# untitled.net
KiCad netlist of a schematic drawn in EAGLE
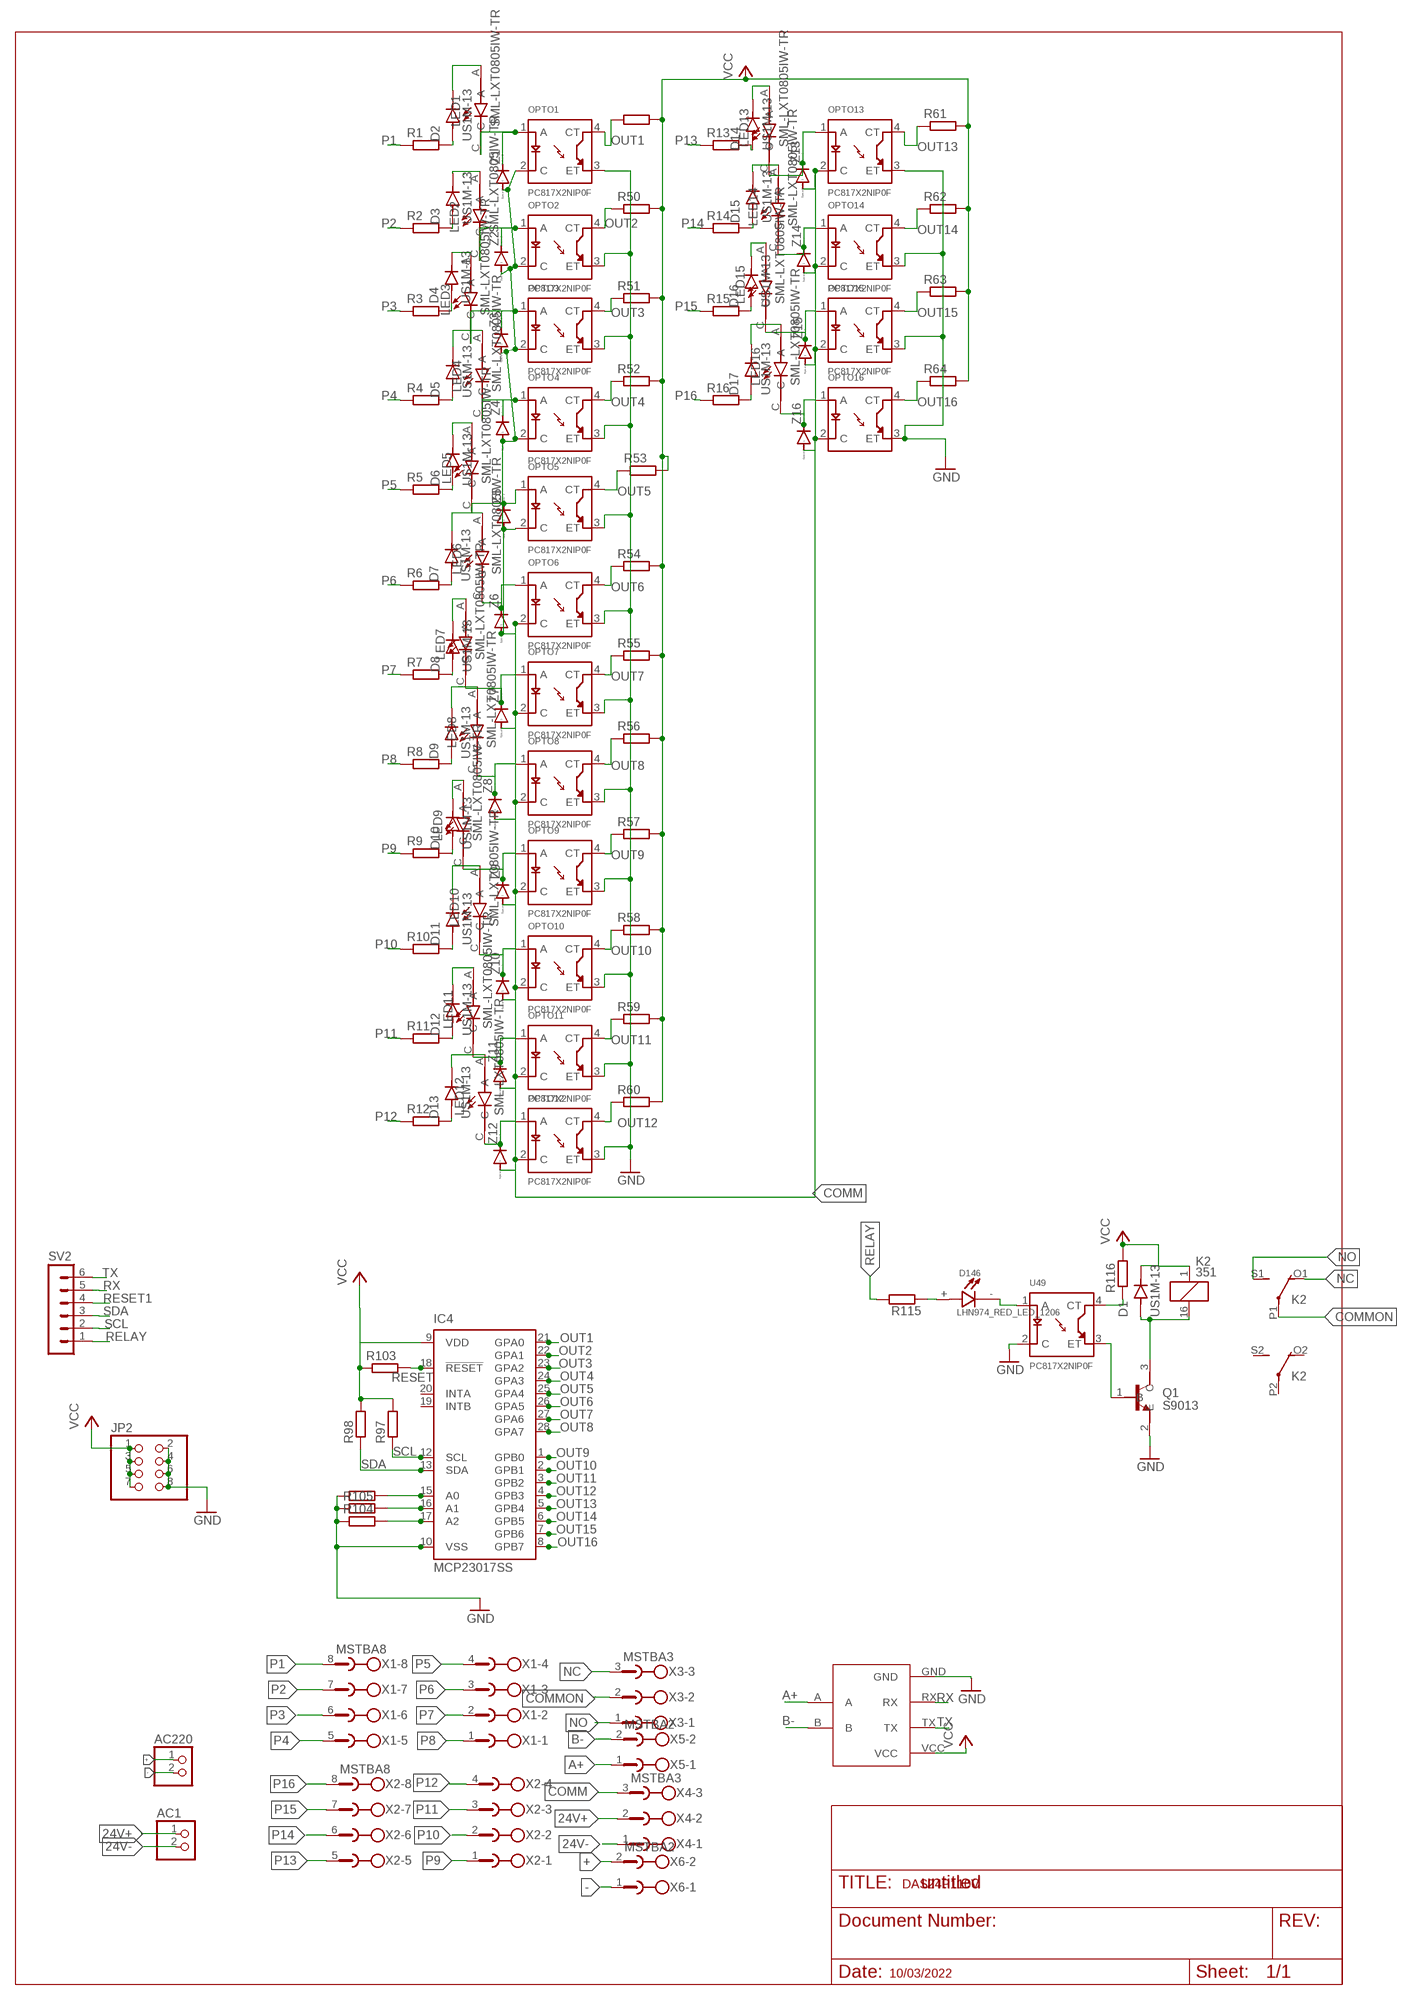
[diagram p0: schematic, sheet 1]

(export (version "E")
  (design (tool "Eeschema 10.0.6"))
  (components
    (comp (ref "AC1")
      (value "PINHD-1X2")
      (footprint "eagle-import:1X02")
      (libsource (lib "eagle-import") (part "PINHD-1X2"))
    )
    (comp (ref "AC220")
      (value "PINHD-1X2")
      (footprint "eagle-import:1X02")
      (libsource (lib "eagle-import") (part "PINHD-1X2"))
    )
    (comp (ref "D1")
      (value "US1M-13")
      (footprint "eagle-import:DIOM5226X240N")
      (fields (field (name "MF") "Diodes Incorporated"))
      (libsource (lib "eagle-import") (part "US1M-13"))
    )
    (comp (ref "D2")
      (value "US1M-13")
      (footprint "eagle-import:DIOM5226X240N")
      (fields (field (name "MF") "Diodes Incorporated"))
      (libsource (lib "eagle-import") (part "US1M-13"))
    )
    (comp (ref "D3")
      (value "US1M-13")
      (footprint "eagle-import:DIOM5226X240N")
      (fields (field (name "MF") "Diodes Incorporated"))
      (libsource (lib "eagle-import") (part "US1M-13"))
    )
    (comp (ref "D4")
      (value "US1M-13")
      (footprint "eagle-import:DIOM5226X240N")
      (fields (field (name "MF") "Diodes Incorporated"))
      (libsource (lib "eagle-import") (part "US1M-13"))
    )
    (comp (ref "D5")
      (value "US1M-13")
      (footprint "eagle-import:DIOM5226X240N")
      (fields (field (name "MF") "Diodes Incorporated"))
      (libsource (lib "eagle-import") (part "US1M-13"))
    )
    (comp (ref "D6")
      (value "US1M-13")
      (footprint "eagle-import:DIOM5226X240N")
      (fields (field (name "MF") "Diodes Incorporated"))
      (libsource (lib "eagle-import") (part "US1M-13"))
    )
    (comp (ref "D7")
      (value "US1M-13")
      (footprint "eagle-import:DIOM5226X240N")
      (fields (field (name "MF") "Diodes Incorporated"))
      (libsource (lib "eagle-import") (part "US1M-13"))
    )
    (comp (ref "D8")
      (value "US1M-13")
      (footprint "eagle-import:DIOM5226X240N")
      (fields (field (name "MF") "Diodes Incorporated"))
      (libsource (lib "eagle-import") (part "US1M-13"))
    )
    (comp (ref "D9")
      (value "US1M-13")
      (footprint "eagle-import:DIOM5226X240N")
      (fields (field (name "MF") "Diodes Incorporated"))
      (libsource (lib "eagle-import") (part "US1M-13"))
    )
    (comp (ref "D10")
      (value "US1M-13")
      (footprint "eagle-import:DIOM5226X240N")
      (fields (field (name "MF") "Diodes Incorporated"))
      (libsource (lib "eagle-import") (part "US1M-13"))
    )
    (comp (ref "D11")
      (value "US1M-13")
      (footprint "eagle-import:DIOM5226X240N")
      (fields (field (name "MF") "Diodes Incorporated"))
      (libsource (lib "eagle-import") (part "US1M-13"))
    )
    (comp (ref "D12")
      (value "US1M-13")
      (footprint "eagle-import:DIOM5226X240N")
      (fields (field (name "MF") "Diodes Incorporated"))
      (libsource (lib "eagle-import") (part "US1M-13"))
    )
    (comp (ref "D13")
      (value "US1M-13")
      (footprint "eagle-import:DIOM5226X240N")
      (fields (field (name "MF") "Diodes Incorporated"))
      (libsource (lib "eagle-import") (part "US1M-13"))
    )
    (comp (ref "D14")
      (value "US1M-13")
      (footprint "eagle-import:DIOM5226X240N")
      (fields (field (name "MF") "Diodes Incorporated"))
      (libsource (lib "eagle-import") (part "US1M-13"))
    )
    (comp (ref "D15")
      (value "US1M-13")
      (footprint "eagle-import:DIOM5226X240N")
      (fields (field (name "MF") "Diodes Incorporated"))
      (libsource (lib "eagle-import") (part "US1M-13"))
    )
    (comp (ref "D16")
      (value "US1M-13")
      (footprint "eagle-import:DIOM5226X240N")
      (fields (field (name "MF") "Diodes Incorporated"))
      (libsource (lib "eagle-import") (part "US1M-13"))
    )
    (comp (ref "D17")
      (value "US1M-13")
      (footprint "eagle-import:DIOM5226X240N")
      (fields (field (name "MF") "Diodes Incorporated"))
      (libsource (lib "eagle-import") (part "US1M-13"))
    )
    (comp (ref "D146")
      (value "LHN974_RED_LED_1206")
      (footprint "eagle-import:LEDC3216X120N")
      (fields (field (name "MF") "Osram") (field (name "MP") "LHN974 RED LED 1206"))
      (libsource (lib "eagle-import") (part "LHN974_RED_LED_1206"))
    )
    (comp (ref "IC4")
      (value "MCP23017SS")
      (footprint "eagle-import:SSOP28DB")
      (libsource (lib "eagle-import") (part "MCP23017SS"))
    )
    (comp (ref "JP2")
      (value "PINHD-2X4")
      (footprint "eagle-import:2X04")
      (libsource (lib "eagle-import") (part "PINHD-2X4"))
    )
    (comp (ref "K2")
      (value "351")
      (footprint "eagle-import:351")
      (libsource (lib "eagle-import") (part "351"))
    )
    (comp (ref "LED1")
      (value "SML-LXT0805IW-TR")
      (footprint "eagle-import:LEDC2012X120N")
      (fields (field (name "MF") "Lumex Opto/Components"))
      (libsource (lib "eagle-import") (part "SML-LXT0805IW-TR"))
    )
    (comp (ref "LED2")
      (value "SML-LXT0805IW-TR")
      (footprint "eagle-import:LEDC2012X120N")
      (fields (field (name "MF") "Lumex Opto/Components"))
      (libsource (lib "eagle-import") (part "SML-LXT0805IW-TR"))
    )
    (comp (ref "LED3")
      (value "SML-LXT0805IW-TR")
      (footprint "eagle-import:LEDC2012X120N")
      (fields (field (name "MF") "Lumex Opto/Components"))
      (libsource (lib "eagle-import") (part "SML-LXT0805IW-TR"))
    )
    (comp (ref "LED4")
      (value "SML-LXT0805IW-TR")
      (footprint "eagle-import:LEDC2012X120N")
      (fields (field (name "MF") "Lumex Opto/Components"))
      (libsource (lib "eagle-import") (part "SML-LXT0805IW-TR"))
    )
    (comp (ref "LED5")
      (value "SML-LXT0805IW-TR")
      (footprint "eagle-import:LEDC2012X120N")
      (fields (field (name "MF") "Lumex Opto/Components"))
      (libsource (lib "eagle-import") (part "SML-LXT0805IW-TR"))
    )
    (comp (ref "LED6")
      (value "SML-LXT0805IW-TR")
      (footprint "eagle-import:LEDC2012X120N")
      (fields (field (name "MF") "Lumex Opto/Components"))
      (libsource (lib "eagle-import") (part "SML-LXT0805IW-TR"))
    )
    (comp (ref "LED7")
      (value "SML-LXT0805IW-TR")
      (footprint "eagle-import:LEDC2012X120N")
      (fields (field (name "MF") "Lumex Opto/Components"))
      (libsource (lib "eagle-import") (part "SML-LXT0805IW-TR"))
    )
    (comp (ref "LED8")
      (value "SML-LXT0805IW-TR")
      (footprint "eagle-import:LEDC2012X120N")
      (fields (field (name "MF") "Lumex Opto/Components"))
      (libsource (lib "eagle-import") (part "SML-LXT0805IW-TR"))
    )
    (comp (ref "LED9")
      (value "SML-LXT0805IW-TR")
      (footprint "eagle-import:LEDC2012X120N")
      (fields (field (name "MF") "Lumex Opto/Components"))
      (libsource (lib "eagle-import") (part "SML-LXT0805IW-TR"))
    )
    (comp (ref "LED10")
      (value "SML-LXT0805IW-TR")
      (footprint "eagle-import:LEDC2012X120N")
      (fields (field (name "MF") "Lumex Opto/Components"))
      (libsource (lib "eagle-import") (part "SML-LXT0805IW-TR"))
    )
    (comp (ref "LED11")
      (value "SML-LXT0805IW-TR")
      (footprint "eagle-import:LEDC2012X120N")
      (fields (field (name "MF") "Lumex Opto/Components"))
      (libsource (lib "eagle-import") (part "SML-LXT0805IW-TR"))
    )
    (comp (ref "LED12")
      (value "SML-LXT0805IW-TR")
      (footprint "eagle-import:LEDC2012X120N")
      (fields (field (name "MF") "Lumex Opto/Components"))
      (libsource (lib "eagle-import") (part "SML-LXT0805IW-TR"))
    )
    (comp (ref "LED13")
      (value "SML-LXT0805IW-TR")
      (footprint "eagle-import:LEDC2012X120N")
      (fields (field (name "MF") "Lumex Opto/Components"))
      (libsource (lib "eagle-import") (part "SML-LXT0805IW-TR"))
    )
    (comp (ref "LED14")
      (value "SML-LXT0805IW-TR")
      (footprint "eagle-import:LEDC2012X120N")
      (fields (field (name "MF") "Lumex Opto/Components"))
      (libsource (lib "eagle-import") (part "SML-LXT0805IW-TR"))
    )
    (comp (ref "LED15")
      (value "SML-LXT0805IW-TR")
      (footprint "eagle-import:LEDC2012X120N")
      (fields (field (name "MF") "Lumex Opto/Components"))
      (libsource (lib "eagle-import") (part "SML-LXT0805IW-TR"))
    )
    (comp (ref "LED16")
      (value "SML-LXT0805IW-TR")
      (footprint "eagle-import:LEDC2012X120N")
      (fields (field (name "MF") "Lumex Opto/Components"))
      (libsource (lib "eagle-import") (part "SML-LXT0805IW-TR"))
    )
    (comp (ref "OPTO1")
      (value "PC817X2NIP0F")
      (footprint "eagle-import:SOT254P975X400-4N")
      (fields (field (name "MF") "Sharp Microelectronics"))
      (libsource (lib "eagle-import") (part "PC817X2NIP0F"))
    )
    (comp (ref "OPTO2")
      (value "PC817X2NIP0F")
      (footprint "eagle-import:SOT254P975X400-4N")
      (fields (field (name "MF") "Sharp Microelectronics"))
      (libsource (lib "eagle-import") (part "PC817X2NIP0F"))
    )
    (comp (ref "OPTO3")
      (value "PC817X2NIP0F")
      (footprint "eagle-import:SOT254P975X400-4N")
      (fields (field (name "MF") "Sharp Microelectronics"))
      (libsource (lib "eagle-import") (part "PC817X2NIP0F"))
    )
    (comp (ref "OPTO4")
      (value "PC817X2NIP0F")
      (footprint "eagle-import:SOT254P975X400-4N")
      (fields (field (name "MF") "Sharp Microelectronics"))
      (libsource (lib "eagle-import") (part "PC817X2NIP0F"))
    )
    (comp (ref "OPTO5")
      (value "PC817X2NIP0F")
      (footprint "eagle-import:SOT254P975X400-4N")
      (fields (field (name "MF") "Sharp Microelectronics"))
      (libsource (lib "eagle-import") (part "PC817X2NIP0F"))
    )
    (comp (ref "OPTO6")
      (value "PC817X2NIP0F")
      (footprint "eagle-import:SOT254P975X400-4N")
      (fields (field (name "MF") "Sharp Microelectronics"))
      (libsource (lib "eagle-import") (part "PC817X2NIP0F"))
    )
    (comp (ref "OPTO7")
      (value "PC817X2NIP0F")
      (footprint "eagle-import:SOT254P975X400-4N")
      (fields (field (name "MF") "Sharp Microelectronics"))
      (libsource (lib "eagle-import") (part "PC817X2NIP0F"))
    )
    (comp (ref "OPTO8")
      (value "PC817X2NIP0F")
      (footprint "eagle-import:SOT254P975X400-4N")
      (fields (field (name "MF") "Sharp Microelectronics"))
      (libsource (lib "eagle-import") (part "PC817X2NIP0F"))
    )
    (comp (ref "OPTO9")
      (value "PC817X2NIP0F")
      (footprint "eagle-import:SOT254P975X400-4N")
      (fields (field (name "MF") "Sharp Microelectronics"))
      (libsource (lib "eagle-import") (part "PC817X2NIP0F"))
    )
    (comp (ref "OPTO10")
      (value "PC817X2NIP0F")
      (footprint "eagle-import:SOT254P975X400-4N")
      (fields (field (name "MF") "Sharp Microelectronics"))
      (libsource (lib "eagle-import") (part "PC817X2NIP0F"))
    )
    (comp (ref "OPTO11")
      (value "PC817X2NIP0F")
      (footprint "eagle-import:SOT254P975X400-4N")
      (fields (field (name "MF") "Sharp Microelectronics"))
      (libsource (lib "eagle-import") (part "PC817X2NIP0F"))
    )
    (comp (ref "OPTO12")
      (value "PC817X2NIP0F")
      (footprint "eagle-import:SOT254P975X400-4N")
      (fields (field (name "MF") "Sharp Microelectronics"))
      (libsource (lib "eagle-import") (part "PC817X2NIP0F"))
    )
    (comp (ref "OPTO13")
      (value "PC817X2NIP0F")
      (footprint "eagle-import:SOT254P975X400-4N")
      (fields (field (name "MF") "Sharp Microelectronics"))
      (libsource (lib "eagle-import") (part "PC817X2NIP0F"))
    )
    (comp (ref "OPTO14")
      (value "PC817X2NIP0F")
      (footprint "eagle-import:SOT254P975X400-4N")
      (fields (field (name "MF") "Sharp Microelectronics"))
      (libsource (lib "eagle-import") (part "PC817X2NIP0F"))
    )
    (comp (ref "OPTO15")
      (value "PC817X2NIP0F")
      (footprint "eagle-import:SOT254P975X400-4N")
      (fields (field (name "MF") "Sharp Microelectronics"))
      (libsource (lib "eagle-import") (part "PC817X2NIP0F"))
    )
    (comp (ref "OPTO16")
      (value "PC817X2NIP0F")
      (footprint "eagle-import:SOT254P975X400-4N")
      (fields (field (name "MF") "Sharp Microelectronics"))
      (libsource (lib "eagle-import") (part "PC817X2NIP0F"))
    )
    (comp (ref "Q1")
      (value "S9013")
      (footprint "eagle-import:SOT95P240X120-3N")
      (fields (field (name "MF") "JCET"))
      (libsource (lib "eagle-import") (part "S9013"))
    )
    (comp (ref "R1")
      (value "R-EU_0414/15")
      (footprint "eagle-import:0414_15")
      (libsource (lib "eagle-import") (part "R-EU_0414/15"))
    )
    (comp (ref "R2")
      (value "R-EU_0414/15")
      (footprint "eagle-import:0414_15")
      (libsource (lib "eagle-import") (part "R-EU_0414/15"))
    )
    (comp (ref "R3")
      (value "R-EU_0414/15")
      (footprint "eagle-import:0414_15")
      (libsource (lib "eagle-import") (part "R-EU_0414/15"))
    )
    (comp (ref "R4")
      (value "R-EU_0414/15")
      (footprint "eagle-import:0414_15")
      (libsource (lib "eagle-import") (part "R-EU_0414/15"))
    )
    (comp (ref "R5")
      (value "R-EU_0414/15")
      (footprint "eagle-import:0414_15")
      (libsource (lib "eagle-import") (part "R-EU_0414/15"))
    )
    (comp (ref "R6")
      (value "R-EU_0414/15")
      (footprint "eagle-import:0414_15")
      (libsource (lib "eagle-import") (part "R-EU_0414/15"))
    )
    (comp (ref "R7")
      (value "R-EU_0414/15")
      (footprint "eagle-import:0414_15")
      (libsource (lib "eagle-import") (part "R-EU_0414/15"))
    )
    (comp (ref "R8")
      (value "R-EU_0414/15")
      (footprint "eagle-import:0414_15")
      (libsource (lib "eagle-import") (part "R-EU_0414/15"))
    )
    (comp (ref "R9")
      (value "R-EU_0414/15")
      (footprint "eagle-import:0414_15")
      (libsource (lib "eagle-import") (part "R-EU_0414/15"))
    )
    (comp (ref "R10")
      (value "R-EU_0414/15")
      (footprint "eagle-import:0414_15")
      (libsource (lib "eagle-import") (part "R-EU_0414/15"))
    )
    (comp (ref "R11")
      (value "R-EU_0414/15")
      (footprint "eagle-import:0414_15")
      (libsource (lib "eagle-import") (part "R-EU_0414/15"))
    )
    (comp (ref "R12")
      (value "R-EU_0414/15")
      (footprint "eagle-import:0414_15")
      (libsource (lib "eagle-import") (part "R-EU_0414/15"))
    )
    (comp (ref "R13")
      (value "R-EU_0414/15")
      (footprint "eagle-import:0414_15")
      (libsource (lib "eagle-import") (part "R-EU_0414/15"))
    )
    (comp (ref "R14")
      (value "R-EU_0414/15")
      (footprint "eagle-import:0414_15")
      (libsource (lib "eagle-import") (part "R-EU_0414/15"))
    )
    (comp (ref "R15")
      (value "R-EU_0414/15")
      (footprint "eagle-import:0414_15")
      (libsource (lib "eagle-import") (part "R-EU_0414/15"))
    )
    (comp (ref "R16")
      (value "R-EU_0414/15")
      (footprint "eagle-import:0414_15")
      (libsource (lib "eagle-import") (part "R-EU_0414/15"))
    )
    (comp (ref "R49")
      (value "R-EU_R0805")
      (footprint "eagle-import:R0805")
      (libsource (lib "eagle-import") (part "R-EU_R0805"))
    )
    (comp (ref "R50")
      (value "R-EU_R0805")
      (footprint "eagle-import:R0805")
      (libsource (lib "eagle-import") (part "R-EU_R0805"))
    )
    (comp (ref "R51")
      (value "R-EU_R0805")
      (footprint "eagle-import:R0805")
      (libsource (lib "eagle-import") (part "R-EU_R0805"))
    )
    (comp (ref "R52")
      (value "R-EU_R0805")
      (footprint "eagle-import:R0805")
      (libsource (lib "eagle-import") (part "R-EU_R0805"))
    )
    (comp (ref "R53")
      (value "R-EU_R0805")
      (footprint "eagle-import:R0805")
      (libsource (lib "eagle-import") (part "R-EU_R0805"))
    )
    (comp (ref "R54")
      (value "R-EU_R0805")
      (footprint "eagle-import:R0805")
      (libsource (lib "eagle-import") (part "R-EU_R0805"))
    )
    (comp (ref "R55")
      (value "R-EU_R0805")
      (footprint "eagle-import:R0805")
      (libsource (lib "eagle-import") (part "R-EU_R0805"))
    )
    (comp (ref "R56")
      (value "R-EU_R0805")
      (footprint "eagle-import:R0805")
      (libsource (lib "eagle-import") (part "R-EU_R0805"))
    )
    (comp (ref "R57")
      (value "R-EU_R0805")
      (footprint "eagle-import:R0805")
      (libsource (lib "eagle-import") (part "R-EU_R0805"))
    )
    (comp (ref "R58")
      (value "R-EU_R0805")
      (footprint "eagle-import:R0805")
      (libsource (lib "eagle-import") (part "R-EU_R0805"))
    )
    (comp (ref "R59")
      (value "R-EU_R0805")
      (footprint "eagle-import:R0805")
      (libsource (lib "eagle-import") (part "R-EU_R0805"))
    )
    (comp (ref "R60")
      (value "R-EU_R0805")
      (footprint "eagle-import:R0805")
      (libsource (lib "eagle-import") (part "R-EU_R0805"))
    )
    (comp (ref "R61")
      (value "R-EU_R0805")
      (footprint "eagle-import:R0805")
      (libsource (lib "eagle-import") (part "R-EU_R0805"))
    )
    (comp (ref "R62")
      (value "R-EU_R0805")
      (footprint "eagle-import:R0805")
      (libsource (lib "eagle-import") (part "R-EU_R0805"))
    )
    (comp (ref "R63")
      (value "R-EU_R0805")
      (footprint "eagle-import:R0805")
      (libsource (lib "eagle-import") (part "R-EU_R0805"))
    )
    (comp (ref "R64")
      (value "R-EU_R0805")
      (footprint "eagle-import:R0805")
      (libsource (lib "eagle-import") (part "R-EU_R0805"))
    )
    (comp (ref "R97")
      (value "R-EU_R0805")
      (footprint "eagle-import:R0805")
      (libsource (lib "eagle-import") (part "R-EU_R0805"))
    )
    (comp (ref "R98")
      (value "R-EU_R0805")
      (footprint "eagle-import:R0805")
      (libsource (lib "eagle-import") (part "R-EU_R0805"))
    )
    (comp (ref "R103")
      (value "R-EU_R0805")
      (footprint "eagle-import:R0805")
      (libsource (lib "eagle-import") (part "R-EU_R0805"))
    )
    (comp (ref "R104")
      (value "R-EU_R0805")
      (footprint "eagle-import:R0805")
      (libsource (lib "eagle-import") (part "R-EU_R0805"))
    )
    (comp (ref "R105")
      (value "R-EU_R0805")
      (footprint "eagle-import:R0805")
      (libsource (lib "eagle-import") (part "R-EU_R0805"))
    )
    (comp (ref "R106")
      (value "R-EU_R0805")
      (footprint "eagle-import:R0805")
      (libsource (lib "eagle-import") (part "R-EU_R0805"))
    )
    (comp (ref "R115")
      (value "R-EU_R0805")
      (footprint "eagle-import:R0805")
      (libsource (lib "eagle-import") (part "R-EU_R0805"))
    )
    (comp (ref "R116")
      (value "R-EU_R0805")
      (footprint "eagle-import:R0805")
      (libsource (lib "eagle-import") (part "R-EU_R0805"))
    )
    (comp (ref "SV2")
      (value "MA06-1")
      (footprint "eagle-import:MA06-1")
      (libsource (lib "eagle-import") (part "MA06-1"))
    )
    (comp (ref "TTL-RS1")
      (value "TTL-RS485")
      (footprint "eagle-import:TTL-RS485")
      (libsource (lib "eagle-import") (part "TTL-RS485"))
    )
    (comp (ref "U49")
      (value "PC817X2NIP0F")
      (footprint "eagle-import:SOT254P975X400-4N")
      (fields (field (name "MF") "Sharp Microelectronics"))
      (libsource (lib "eagle-import") (part "PC817X2NIP0F"))
    )
    (comp (ref "X1")
      (value "MSTBA8")
      (footprint "eagle-import:MSTBA8")
      (fields (field (name "MF") "FARNELL") (field (name "MPN") "1757307"))
      (libsource (lib "eagle-import") (part "MSTBA8"))
    )
    (comp (ref "X2")
      (value "MSTBA8")
      (footprint "eagle-import:MSTBA8")
      (fields (field (name "MF") "FARNELL") (field (name "MPN") "1757307"))
      (libsource (lib "eagle-import") (part "MSTBA8"))
    )
    (comp (ref "X3")
      (value "MSTBA3")
      (footprint "eagle-import:MSTBA3")
      (fields (field (name "MF") "FARNELL") (field (name "MPN") "1757255"))
      (libsource (lib "eagle-import") (part "MSTBA3"))
    )
    (comp (ref "X4")
      (value "MSTBA3")
      (footprint "eagle-import:MSTBA3")
      (fields (field (name "MF") "FARNELL") (field (name "MPN") "1757255"))
      (libsource (lib "eagle-import") (part "MSTBA3"))
    )
    (comp (ref "X5")
      (value "MSTBA2")
      (footprint "eagle-import:MSTBA2")
      (fields (field (name "MF") "FARNELL") (field (name "MPN") "1757242"))
      (libsource (lib "eagle-import") (part "MSTBA2"))
    )
    (comp (ref "X6")
      (value "MSTBA2")
      (footprint "eagle-import:MSTBA2")
      (fields (field (name "MF") "FARNELL") (field (name "MPN") "1757242"))
      (libsource (lib "eagle-import") (part "MSTBA2"))
    )
    (comp (ref "Z1")
      (value "DIODE-SOD123")
      (footprint "eagle-import:SOD123")
      (libsource (lib "eagle-import") (part "DIODE-SOD123"))
    )
    (comp (ref "Z2")
      (value "DIODE-SOD123")
      (footprint "eagle-import:SOD123")
      (libsource (lib "eagle-import") (part "DIODE-SOD123"))
    )
    (comp (ref "Z3")
      (value "DIODE-SOD123")
      (footprint "eagle-import:SOD123")
      (libsource (lib "eagle-import") (part "DIODE-SOD123"))
    )
    (comp (ref "Z4")
      (value "DIODE-SOD123")
      (footprint "eagle-import:SOD123")
      (libsource (lib "eagle-import") (part "DIODE-SOD123"))
    )
    (comp (ref "Z5")
      (value "DIODE-SOD123")
      (footprint "eagle-import:SOD123")
      (libsource (lib "eagle-import") (part "DIODE-SOD123"))
    )
    (comp (ref "Z6")
      (value "DIODE-SOD123")
      (footprint "eagle-import:SOD123")
      (libsource (lib "eagle-import") (part "DIODE-SOD123"))
    )
    (comp (ref "Z7")
      (value "DIODE-SOD123")
      (footprint "eagle-import:SOD123")
      (libsource (lib "eagle-import") (part "DIODE-SOD123"))
    )
    (comp (ref "Z8")
      (value "DIODE-SOD123")
      (footprint "eagle-import:SOD123")
      (libsource (lib "eagle-import") (part "DIODE-SOD123"))
    )
    (comp (ref "Z9")
      (value "DIODE-SOD123")
      (footprint "eagle-import:SOD123")
      (libsource (lib "eagle-import") (part "DIODE-SOD123"))
    )
    (comp (ref "Z10")
      (value "DIODE-SOD123")
      (footprint "eagle-import:SOD123")
      (libsource (lib "eagle-import") (part "DIODE-SOD123"))
    )
    (comp (ref "Z11")
      (value "DIODE-SOD123")
      (footprint "eagle-import:SOD123")
      (libsource (lib "eagle-import") (part "DIODE-SOD123"))
    )
    (comp (ref "Z12")
      (value "DIODE-SOD123")
      (footprint "eagle-import:SOD123")
      (libsource (lib "eagle-import") (part "DIODE-SOD123"))
    )
    (comp (ref "Z13")
      (value "DIODE-SOD123")
      (footprint "eagle-import:SOD123")
      (libsource (lib "eagle-import") (part "DIODE-SOD123"))
    )
    (comp (ref "Z14")
      (value "DIODE-SOD123")
      (footprint "eagle-import:SOD123")
      (libsource (lib "eagle-import") (part "DIODE-SOD123"))
    )
    (comp (ref "Z15")
      (value "DIODE-SOD123")
      (footprint "eagle-import:SOD123")
      (libsource (lib "eagle-import") (part "DIODE-SOD123"))
    )
    (comp (ref "Z16")
      (value "DIODE-SOD123")
      (footprint "eagle-import:SOD123")
      (libsource (lib "eagle-import") (part "DIODE-SOD123"))
    )
  )
  (nets
    (net (code "1") (name "+") (class "Default")
      (node (ref "AC220") (pin "1") (pinfunction "1_1") (pintype "passive"))
      (node (ref "X6") (pin "2") (pinfunction "1_2") (pintype "passive"))
    )
    (net (code "2") (name "-") (class "Default")
      (node (ref "AC220") (pin "2") (pinfunction "2_2") (pintype "passive"))
      (node (ref "X6") (pin "1") (pinfunction "1_1") (pintype "passive"))
    )
    (net (code "3") (name "/OUT1") (class "Default")
      (node (ref "IC4") (pin "21") (pinfunction "GPA0_21") (pintype "bidirectional"))
      (node (ref "OPTO1") (pin "4") (pinfunction "CT_4") (pintype "passive"))
      (node (ref "R49") (pin "1") (pinfunction "1_1") (pintype "passive"))
    )
    (net (code "4") (name "/OUT2") (class "Default")
      (node (ref "IC4") (pin "22") (pinfunction "GPA1_22") (pintype "bidirectional"))
      (node (ref "OPTO2") (pin "4") (pinfunction "CT_4") (pintype "passive"))
      (node (ref "R50") (pin "1") (pinfunction "1_1") (pintype "passive"))
    )
    (net (code "5") (name "/OUT3") (class "Default")
      (node (ref "IC4") (pin "23") (pinfunction "GPA2_23") (pintype "bidirectional"))
      (node (ref "OPTO3") (pin "4") (pinfunction "CT_4") (pintype "passive"))
      (node (ref "R51") (pin "1") (pinfunction "1_1") (pintype "passive"))
    )
    (net (code "6") (name "/OUT4") (class "Default")
      (node (ref "IC4") (pin "24") (pinfunction "GPA3_24") (pintype "bidirectional"))
      (node (ref "OPTO4") (pin "4") (pinfunction "CT_4") (pintype "passive"))
      (node (ref "R52") (pin "1") (pinfunction "1_1") (pintype "passive"))
    )
    (net (code "7") (name "/OUT5") (class "Default")
      (node (ref "IC4") (pin "25") (pinfunction "GPA4_25") (pintype "bidirectional"))
      (node (ref "OPTO5") (pin "4") (pinfunction "CT_4") (pintype "passive"))
      (node (ref "R53") (pin "1") (pinfunction "1_1") (pintype "passive"))
    )
    (net (code "8") (name "/OUT6") (class "Default")
      (node (ref "IC4") (pin "26") (pinfunction "GPA5_26") (pintype "bidirectional"))
      (node (ref "OPTO6") (pin "4") (pinfunction "CT_4") (pintype "passive"))
      (node (ref "R54") (pin "1") (pinfunction "1_1") (pintype "passive"))
    )
    (net (code "9") (name "/OUT7") (class "Default")
      (node (ref "IC4") (pin "27") (pinfunction "GPA6_27") (pintype "bidirectional"))
      (node (ref "OPTO7") (pin "4") (pinfunction "CT_4") (pintype "passive"))
      (node (ref "R55") (pin "1") (pinfunction "1_1") (pintype "passive"))
    )
    (net (code "10") (name "/OUT8") (class "Default")
      (node (ref "IC4") (pin "28") (pinfunction "GPA7_28") (pintype "bidirectional"))
      (node (ref "OPTO8") (pin "4") (pinfunction "CT_4") (pintype "passive"))
      (node (ref "R56") (pin "1") (pinfunction "1_1") (pintype "passive"))
    )
    (net (code "11") (name "/OUT9") (class "Default")
      (node (ref "IC4") (pin "1") (pinfunction "GPB0_1") (pintype "bidirectional"))
      (node (ref "OPTO9") (pin "4") (pinfunction "CT_4") (pintype "passive"))
      (node (ref "R57") (pin "1") (pinfunction "1_1") (pintype "passive"))
    )
    (net (code "12") (name "/OUT10") (class "Default")
      (node (ref "IC4") (pin "2") (pinfunction "GPB1_2") (pintype "bidirectional"))
      (node (ref "OPTO10") (pin "4") (pinfunction "CT_4") (pintype "passive"))
      (node (ref "R58") (pin "1") (pinfunction "1_1") (pintype "passive"))
    )
    (net (code "13") (name "/OUT11") (class "Default")
      (node (ref "IC4") (pin "3") (pinfunction "GPB2_3") (pintype "bidirectional"))
      (node (ref "OPTO11") (pin "4") (pinfunction "CT_4") (pintype "passive"))
      (node (ref "R59") (pin "1") (pinfunction "1_1") (pintype "passive"))
    )
    (net (code "14") (name "/OUT12") (class "Default")
      (node (ref "IC4") (pin "4") (pinfunction "GPB3_4") (pintype "bidirectional"))
      (node (ref "OPTO12") (pin "4") (pinfunction "CT_4") (pintype "passive"))
      (node (ref "R60") (pin "1") (pinfunction "1_1") (pintype "passive"))
    )
    (net (code "15") (name "/OUT13") (class "Default")
      (node (ref "IC4") (pin "5") (pinfunction "GPB4_5") (pintype "bidirectional"))
      (node (ref "OPTO13") (pin "4") (pinfunction "CT_4") (pintype "passive"))
      (node (ref "R61") (pin "1") (pinfunction "1_1") (pintype "passive"))
    )
    (net (code "16") (name "/OUT14") (class "Default")
      (node (ref "IC4") (pin "6") (pinfunction "GPB5_6") (pintype "bidirectional"))
      (node (ref "OPTO14") (pin "4") (pinfunction "CT_4") (pintype "passive"))
      (node (ref "R62") (pin "1") (pinfunction "1_1") (pintype "passive"))
    )
    (net (code "17") (name "/OUT15") (class "Default")
      (node (ref "IC4") (pin "7") (pinfunction "GPB6_7") (pintype "bidirectional"))
      (node (ref "OPTO15") (pin "4") (pinfunction "CT_4") (pintype "passive"))
      (node (ref "R63") (pin "1") (pinfunction "1_1") (pintype "passive"))
    )
    (net (code "18") (name "/OUT16") (class "Default")
      (node (ref "IC4") (pin "8") (pinfunction "GPB7_8") (pintype "bidirectional"))
      (node (ref "OPTO16") (pin "4") (pinfunction "CT_4") (pintype "passive"))
      (node (ref "R64") (pin "1") (pinfunction "1_1") (pintype "passive"))
    )
    (net (code "19") (name "/RESET") (class "Default")
      (node (ref "IC4") (pin "18") (pinfunction "~{RESET}_18") (pintype "input"))
      (node (ref "R103") (pin "2") (pinfunction "2_2") (pintype "passive"))
    )
    (net (code "20") (name "/RESET1") (class "Default")
      (node (ref "SV2") (pin "4") (pinfunction "4_4") (pintype "passive"))
    )
    (net (code "21") (name "/RX") (class "Default")
      (node (ref "SV2") (pin "5") (pinfunction "5_5") (pintype "passive"))
      (node (ref "TTL-RS1") (pin "RX") (pinfunction "RX_RX") (pintype "bidirectional"))
    )
    (net (code "22") (name "/SCL") (class "Default")
      (node (ref "IC4") (pin "12") (pinfunction "SCL_12") (pintype "input"))
      (node (ref "R97") (pin "1") (pinfunction "1_1") (pintype "passive"))
      (node (ref "SV2") (pin "2") (pinfunction "2_2") (pintype "passive"))
    )
    (net (code "23") (name "/SDA") (class "Default")
      (node (ref "IC4") (pin "13") (pinfunction "SDA_13") (pintype "bidirectional"))
      (node (ref "R98") (pin "1") (pinfunction "1_1") (pintype "passive"))
      (node (ref "SV2") (pin "3") (pinfunction "3_3") (pintype "passive"))
    )
    (net (code "24") (name "/TX") (class "Default")
      (node (ref "SV2") (pin "6") (pinfunction "6_6") (pintype "passive"))
      (node (ref "TTL-RS1") (pin "TX") (pinfunction "TX_TX") (pintype "bidirectional"))
    )
    (net (code "25") (name "24V+") (class "Default")
      (node (ref "AC1") (pin "1") (pinfunction "1_1") (pintype "passive"))
      (node (ref "X4") (pin "2") (pinfunction "1_2") (pintype "passive"))
    )
    (net (code "26") (name "24V-") (class "Default")
      (node (ref "AC1") (pin "2") (pinfunction "2_2") (pintype "passive"))
      (node (ref "X4") (pin "1") (pinfunction "1_1") (pintype "passive"))
    )
    (net (code "27") (name "A+") (class "Default")
      (node (ref "TTL-RS1") (pin "A") (pinfunction "A_A") (pintype "bidirectional"))
      (node (ref "X5") (pin "1") (pinfunction "1_1") (pintype "passive"))
    )
    (net (code "28") (name "B-") (class "Default")
      (node (ref "TTL-RS1") (pin "B") (pinfunction "B_B") (pintype "bidirectional"))
      (node (ref "X5") (pin "2") (pinfunction "1_2") (pintype "passive"))
    )
    (net (code "29") (name "COMM") (class "Default")
      (node (ref "OPTO1") (pin "2") (pinfunction "C_2") (pintype "passive"))
      (node (ref "OPTO10") (pin "2") (pinfunction "C_2") (pintype "passive"))
      (node (ref "OPTO11") (pin "2") (pinfunction "C_2") (pintype "passive"))
      (node (ref "OPTO12") (pin "2") (pinfunction "C_2") (pintype "passive"))
      (node (ref "OPTO13") (pin "2") (pinfunction "C_2") (pintype "passive"))
      (node (ref "OPTO14") (pin "2") (pinfunction "C_2") (pintype "passive"))
      (node (ref "OPTO15") (pin "2") (pinfunction "C_2") (pintype "passive"))
      (node (ref "OPTO16") (pin "2") (pinfunction "C_2") (pintype "passive"))
      (node (ref "OPTO2") (pin "2") (pinfunction "C_2") (pintype "passive"))
      (node (ref "OPTO3") (pin "2") (pinfunction "C_2") (pintype "passive"))
      (node (ref "OPTO4") (pin "2") (pinfunction "C_2") (pintype "passive"))
      (node (ref "OPTO5") (pin "2") (pinfunction "C_2") (pintype "passive"))
      (node (ref "OPTO6") (pin "2") (pinfunction "C_2") (pintype "passive"))
      (node (ref "OPTO7") (pin "2") (pinfunction "C_2") (pintype "passive"))
      (node (ref "OPTO8") (pin "2") (pinfunction "C_2") (pintype "passive"))
      (node (ref "OPTO9") (pin "2") (pinfunction "C_2") (pintype "passive"))
      (node (ref "X4") (pin "3") (pinfunction "1_3") (pintype "passive"))
      (node (ref "Z1") (pin "A") (pinfunction "A_A") (pintype "passive"))
      (node (ref "Z10") (pin "A") (pinfunction "A_A") (pintype "passive"))
      (node (ref "Z11") (pin "A") (pinfunction "A_A") (pintype "passive"))
      (node (ref "Z12") (pin "A") (pinfunction "A_A") (pintype "passive"))
      (node (ref "Z13") (pin "A") (pinfunction "A_A") (pintype "passive"))
      (node (ref "Z14") (pin "A") (pinfunction "A_A") (pintype "passive"))
      (node (ref "Z15") (pin "A") (pinfunction "A_A") (pintype "passive"))
      (node (ref "Z16") (pin "A") (pinfunction "A_A") (pintype "passive"))
      (node (ref "Z2") (pin "A") (pinfunction "A_A") (pintype "passive"))
      (node (ref "Z3") (pin "A") (pinfunction "A_A") (pintype "passive"))
      (node (ref "Z4") (pin "A") (pinfunction "A_A") (pintype "passive"))
      (node (ref "Z5") (pin "A") (pinfunction "A_A") (pintype "passive"))
      (node (ref "Z6") (pin "A") (pinfunction "A_A") (pintype "passive"))
      (node (ref "Z7") (pin "A") (pinfunction "A_A") (pintype "passive"))
      (node (ref "Z8") (pin "A") (pinfunction "A_A") (pintype "passive"))
      (node (ref "Z9") (pin "A") (pinfunction "A_A") (pintype "passive"))
    )
    (net (code "30") (name "COMMON") (class "Default")
      (node (ref "K2") (pin "P1") (pinfunction "P_P1") (pintype "passive"))
      (node (ref "X3") (pin "2") (pinfunction "1_2") (pintype "passive"))
    )
    (net (code "31") (name "GND") (class "Default")
      (node (ref "IC4") (pin "10") (pinfunction "VSS_10") (pintype "power_in"))
      (node (ref "JP2") (pin "2") (pinfunction "2_2") (pintype "passive"))
      (node (ref "JP2") (pin "4") (pinfunction "4_4") (pintype "passive"))
      (node (ref "JP2") (pin "6") (pinfunction "6_6") (pintype "passive"))
      (node (ref "JP2") (pin "8") (pinfunction "8_8") (pintype "passive"))
      (node (ref "OPTO1") (pin "3") (pinfunction "ET_3") (pintype "passive"))
      (node (ref "OPTO10") (pin "3") (pinfunction "ET_3") (pintype "passive"))
      (node (ref "OPTO11") (pin "3") (pinfunction "ET_3") (pintype "passive"))
      (node (ref "OPTO12") (pin "3") (pinfunction "ET_3") (pintype "passive"))
      (node (ref "OPTO13") (pin "3") (pinfunction "ET_3") (pintype "passive"))
      (node (ref "OPTO14") (pin "3") (pinfunction "ET_3") (pintype "passive"))
      (node (ref "OPTO15") (pin "3") (pinfunction "ET_3") (pintype "passive"))
      (node (ref "OPTO16") (pin "3") (pinfunction "ET_3") (pintype "passive"))
      (node (ref "OPTO2") (pin "3") (pinfunction "ET_3") (pintype "passive"))
      (node (ref "OPTO3") (pin "3") (pinfunction "ET_3") (pintype "passive"))
      (node (ref "OPTO4") (pin "3") (pinfunction "ET_3") (pintype "passive"))
      (node (ref "OPTO5") (pin "3") (pinfunction "ET_3") (pintype "passive"))
      (node (ref "OPTO6") (pin "3") (pinfunction "ET_3") (pintype "passive"))
      (node (ref "OPTO7") (pin "3") (pinfunction "ET_3") (pintype "passive"))
      (node (ref "OPTO8") (pin "3") (pinfunction "ET_3") (pintype "passive"))
      (node (ref "OPTO9") (pin "3") (pinfunction "ET_3") (pintype "passive"))
      (node (ref "Q1") (pin "2") (pinfunction "E_2") (pintype "passive"))
      (node (ref "R104") (pin "1") (pinfunction "1_1") (pintype "passive"))
      (node (ref "R105") (pin "1") (pinfunction "1_1") (pintype "passive"))
      (node (ref "R106") (pin "1") (pinfunction "1_1") (pintype "passive"))
      (node (ref "TTL-RS1") (pin "GND") (pinfunction "GND_GND") (pintype "bidirectional"))
      (node (ref "U49") (pin "2") (pinfunction "C_2") (pintype "passive"))
    )
    (net (code "32") (name "NC") (class "Default")
      (node (ref "K2") (pin "O1") (pinfunction "O_O1") (pintype "passive"))
      (node (ref "X3") (pin "3") (pinfunction "1_3") (pintype "passive"))
    )
    (net (code "33") (name "NO") (class "Default")
      (node (ref "K2") (pin "S1") (pinfunction "S_S1") (pintype "passive"))
      (node (ref "X3") (pin "1") (pinfunction "1_1") (pintype "passive"))
    )
    (net (code "34") (name "Net-(D2-K)") (class "Default")
      (node (ref "D2") (pin "C") (pinfunction "K_C") (pintype "passive"))
      (node (ref "LED1") (pin "A") (pinfunction "A_A") (pintype "passive"))
    )
    (net (code "35") (name "Net-(D2-PadA)") (class "Default")
      (node (ref "D2") (pin "A") (pinfunction "A_A") (pintype "passive"))
      (node (ref "R1") (pin "2") (pinfunction "2_2") (pintype "passive"))
    )
    (net (code "36") (name "Net-(D3-K)") (class "Default")
      (node (ref "D3") (pin "C") (pinfunction "K_C") (pintype "passive"))
      (node (ref "LED2") (pin "A") (pinfunction "A_A") (pintype "passive"))
    )
    (net (code "37") (name "Net-(D3-PadA)") (class "Default")
      (node (ref "D3") (pin "A") (pinfunction "A_A") (pintype "passive"))
      (node (ref "R2") (pin "2") (pinfunction "2_2") (pintype "passive"))
    )
    (net (code "38") (name "Net-(D4-K)") (class "Default")
      (node (ref "D4") (pin "C") (pinfunction "K_C") (pintype "passive"))
      (node (ref "LED3") (pin "A") (pinfunction "A_A") (pintype "passive"))
    )
    (net (code "39") (name "Net-(D4-PadA)") (class "Default")
      (node (ref "D4") (pin "A") (pinfunction "A_A") (pintype "passive"))
      (node (ref "R3") (pin "2") (pinfunction "2_2") (pintype "passive"))
    )
    (net (code "40") (name "Net-(D5-K)") (class "Default")
      (node (ref "D5") (pin "C") (pinfunction "K_C") (pintype "passive"))
      (node (ref "LED4") (pin "A") (pinfunction "A_A") (pintype "passive"))
    )
    (net (code "41") (name "Net-(D5-PadA)") (class "Default")
      (node (ref "D5") (pin "A") (pinfunction "A_A") (pintype "passive"))
      (node (ref "R4") (pin "2") (pinfunction "2_2") (pintype "passive"))
    )
    (net (code "42") (name "Net-(D6-K)") (class "Default")
      (node (ref "D6") (pin "C") (pinfunction "K_C") (pintype "passive"))
      (node (ref "LED5") (pin "A") (pinfunction "A_A") (pintype "passive"))
    )
    (net (code "43") (name "Net-(D6-PadA)") (class "Default")
      (node (ref "D6") (pin "A") (pinfunction "A_A") (pintype "passive"))
      (node (ref "R5") (pin "2") (pinfunction "2_2") (pintype "passive"))
    )
    (net (code "44") (name "Net-(D7-K)") (class "Default")
      (node (ref "D7") (pin "C") (pinfunction "K_C") (pintype "passive"))
      (node (ref "LED6") (pin "A") (pinfunction "A_A") (pintype "passive"))
    )
    (net (code "45") (name "Net-(D7-PadA)") (class "Default")
      (node (ref "D7") (pin "A") (pinfunction "A_A") (pintype "passive"))
      (node (ref "R6") (pin "2") (pinfunction "2_2") (pintype "passive"))
    )
    (net (code "46") (name "Net-(D8-K)") (class "Default")
      (node (ref "D8") (pin "C") (pinfunction "K_C") (pintype "passive"))
      (node (ref "LED7") (pin "A") (pinfunction "A_A") (pintype "passive"))
    )
    (net (code "47") (name "Net-(D8-PadA)") (class "Default")
      (node (ref "D8") (pin "A") (pinfunction "A_A") (pintype "passive"))
      (node (ref "R7") (pin "2") (pinfunction "2_2") (pintype "passive"))
    )
    (net (code "48") (name "Net-(D9-K)") (class "Default")
      (node (ref "D9") (pin "C") (pinfunction "K_C") (pintype "passive"))
      (node (ref "LED8") (pin "A") (pinfunction "A_A") (pintype "passive"))
    )
    (net (code "49") (name "Net-(D9-PadA)") (class "Default")
      (node (ref "D9") (pin "A") (pinfunction "A_A") (pintype "passive"))
      (node (ref "R8") (pin "2") (pinfunction "2_2") (pintype "passive"))
    )
    (net (code "50") (name "Net-(D10-K)") (class "Default")
      (node (ref "D10") (pin "C") (pinfunction "K_C") (pintype "passive"))
      (node (ref "LED9") (pin "A") (pinfunction "A_A") (pintype "passive"))
    )
    (net (code "51") (name "Net-(D10-PadA)") (class "Default")
      (node (ref "D10") (pin "A") (pinfunction "A_A") (pintype "passive"))
      (node (ref "R9") (pin "2") (pinfunction "2_2") (pintype "passive"))
    )
    (net (code "52") (name "Net-(D11-K)") (class "Default")
      (node (ref "D11") (pin "C") (pinfunction "K_C") (pintype "passive"))
      (node (ref "LED10") (pin "A") (pinfunction "A_A") (pintype "passive"))
    )
    (net (code "53") (name "Net-(D11-PadA)") (class "Default")
      (node (ref "D11") (pin "A") (pinfunction "A_A") (pintype "passive"))
      (node (ref "R10") (pin "2") (pinfunction "2_2") (pintype "passive"))
    )
    (net (code "54") (name "Net-(D12-K)") (class "Default")
      (node (ref "D12") (pin "C") (pinfunction "K_C") (pintype "passive"))
      (node (ref "LED11") (pin "A") (pinfunction "A_A") (pintype "passive"))
    )
    (net (code "55") (name "Net-(D12-PadA)") (class "Default")
      (node (ref "D12") (pin "A") (pinfunction "A_A") (pintype "passive"))
      (node (ref "R11") (pin "2") (pinfunction "2_2") (pintype "passive"))
    )
    (net (code "56") (name "Net-(D13-K)") (class "Default")
      (node (ref "D13") (pin "C") (pinfunction "K_C") (pintype "passive"))
      (node (ref "LED12") (pin "A") (pinfunction "A_A") (pintype "passive"))
    )
    (net (code "57") (name "Net-(D13-PadA)") (class "Default")
      (node (ref "D13") (pin "A") (pinfunction "A_A") (pintype "passive"))
      (node (ref "R12") (pin "2") (pinfunction "2_2") (pintype "passive"))
    )
    (net (code "58") (name "Net-(D14-K)") (class "Default")
      (node (ref "D14") (pin "C") (pinfunction "K_C") (pintype "passive"))
      (node (ref "LED13") (pin "A") (pinfunction "A_A") (pintype "passive"))
    )
    (net (code "59") (name "Net-(D14-PadA)") (class "Default")
      (node (ref "D14") (pin "A") (pinfunction "A_A") (pintype "passive"))
      (node (ref "R13") (pin "2") (pinfunction "2_2") (pintype "passive"))
    )
    (net (code "60") (name "Net-(D15-K)") (class "Default")
      (node (ref "D15") (pin "C") (pinfunction "K_C") (pintype "passive"))
      (node (ref "LED14") (pin "A") (pinfunction "A_A") (pintype "passive"))
    )
    (net (code "61") (name "Net-(D15-PadA)") (class "Default")
      (node (ref "D15") (pin "A") (pinfunction "A_A") (pintype "passive"))
      (node (ref "R14") (pin "2") (pinfunction "2_2") (pintype "passive"))
    )
    (net (code "62") (name "Net-(D16-K)") (class "Default")
      (node (ref "D16") (pin "C") (pinfunction "K_C") (pintype "passive"))
      (node (ref "LED15") (pin "A") (pinfunction "A_A") (pintype "passive"))
    )
    (net (code "63") (name "Net-(D16-PadA)") (class "Default")
      (node (ref "D16") (pin "A") (pinfunction "A_A") (pintype "passive"))
      (node (ref "R15") (pin "2") (pinfunction "2_2") (pintype "passive"))
    )
    (net (code "64") (name "Net-(D17-K)") (class "Default")
      (node (ref "D17") (pin "C") (pinfunction "K_C") (pintype "passive"))
      (node (ref "LED16") (pin "A") (pinfunction "A_A") (pintype "passive"))
    )
    (net (code "65") (name "Net-(D17-PadA)") (class "Default")
      (node (ref "D17") (pin "A") (pinfunction "A_A") (pintype "passive"))
      (node (ref "R16") (pin "2") (pinfunction "2_2") (pintype "passive"))
    )
    (net (code "66") (name "Net-(D146-Pad+)") (class "Default")
      (node (ref "D146") (pin "+") (pinfunction "+_+") (pintype "passive"))
      (node (ref "R115") (pin "1") (pinfunction "1_1") (pintype "passive"))
    )
    (net (code "67") (name "Net-(IC4-A0)") (class "Default")
      (node (ref "IC4") (pin "15") (pinfunction "A0_15") (pintype "input"))
      (node (ref "R106") (pin "2") (pinfunction "2_2") (pintype "passive"))
    )
    (net (code "68") (name "Net-(IC4-A1)") (class "Default")
      (node (ref "IC4") (pin "16") (pinfunction "A1_16") (pintype "input"))
      (node (ref "R105") (pin "2") (pinfunction "2_2") (pintype "passive"))
    )
    (net (code "69") (name "Net-(IC4-A2)") (class "Default")
      (node (ref "IC4") (pin "17") (pinfunction "A2_17") (pintype "input"))
      (node (ref "R104") (pin "2") (pinfunction "2_2") (pintype "passive"))
    )
    (net (code "70") (name "Net-(K2A-2)") (class "Default")
      (node (ref "D1") (pin "A") (pinfunction "A_A") (pintype "passive"))
      (node (ref "K2") (pin "16") (pinfunction "2_16") (pintype "passive"))
      (node (ref "Q1") (pin "3") (pinfunction "C_3") (pintype "passive"))
    )
    (net (code "71") (name "Net-(OPTO1-A)") (class "Default")
      (node (ref "LED1") (pin "C") (pinfunction "C_C") (pintype "passive"))
      (node (ref "OPTO1") (pin "1") (pinfunction "A_1") (pintype "passive"))
      (node (ref "Z1") (pin "C") (pinfunction "C_C") (pintype "passive"))
    )
    (net (code "72") (name "Net-(OPTO2-A)") (class "Default")
      (node (ref "LED2") (pin "C") (pinfunction "C_C") (pintype "passive"))
      (node (ref "OPTO2") (pin "1") (pinfunction "A_1") (pintype "passive"))
      (node (ref "Z2") (pin "C") (pinfunction "C_C") (pintype "passive"))
    )
    (net (code "73") (name "Net-(OPTO3-A)") (class "Default")
      (node (ref "LED3") (pin "C") (pinfunction "C_C") (pintype "passive"))
      (node (ref "OPTO3") (pin "1") (pinfunction "A_1") (pintype "passive"))
      (node (ref "Z3") (pin "C") (pinfunction "C_C") (pintype "passive"))
    )
    (net (code "74") (name "Net-(OPTO4-A)") (class "Default")
      (node (ref "LED4") (pin "C") (pinfunction "C_C") (pintype "passive"))
      (node (ref "OPTO4") (pin "1") (pinfunction "A_1") (pintype "passive"))
      (node (ref "Z4") (pin "C") (pinfunction "C_C") (pintype "passive"))
    )
    (net (code "75") (name "Net-(OPTO5-A)") (class "Default")
      (node (ref "LED5") (pin "C") (pinfunction "C_C") (pintype "passive"))
      (node (ref "OPTO5") (pin "1") (pinfunction "A_1") (pintype "passive"))
      (node (ref "Z5") (pin "C") (pinfunction "C_C") (pintype "passive"))
    )
    (net (code "76") (name "Net-(OPTO6-A)") (class "Default")
      (node (ref "LED6") (pin "C") (pinfunction "C_C") (pintype "passive"))
      (node (ref "OPTO6") (pin "1") (pinfunction "A_1") (pintype "passive"))
      (node (ref "Z6") (pin "C") (pinfunction "C_C") (pintype "passive"))
    )
    (net (code "77") (name "Net-(OPTO7-A)") (class "Default")
      (node (ref "LED7") (pin "C") (pinfunction "C_C") (pintype "passive"))
      (node (ref "OPTO7") (pin "1") (pinfunction "A_1") (pintype "passive"))
      (node (ref "Z7") (pin "C") (pinfunction "C_C") (pintype "passive"))
    )
    (net (code "78") (name "Net-(OPTO8-A)") (class "Default")
      (node (ref "LED8") (pin "C") (pinfunction "C_C") (pintype "passive"))
      (node (ref "OPTO8") (pin "1") (pinfunction "A_1") (pintype "passive"))
      (node (ref "Z8") (pin "C") (pinfunction "C_C") (pintype "passive"))
    )
    (net (code "79") (name "Net-(OPTO9-A)") (class "Default")
      (node (ref "LED9") (pin "C") (pinfunction "C_C") (pintype "passive"))
      (node (ref "OPTO9") (pin "1") (pinfunction "A_1") (pintype "passive"))
      (node (ref "Z9") (pin "C") (pinfunction "C_C") (pintype "passive"))
    )
    (net (code "80") (name "Net-(OPTO10-A)") (class "Default")
      (node (ref "LED10") (pin "C") (pinfunction "C_C") (pintype "passive"))
      (node (ref "OPTO10") (pin "1") (pinfunction "A_1") (pintype "passive"))
      (node (ref "Z10") (pin "C") (pinfunction "C_C") (pintype "passive"))
    )
    (net (code "81") (name "Net-(OPTO11-A)") (class "Default")
      (node (ref "LED11") (pin "C") (pinfunction "C_C") (pintype "passive"))
      (node (ref "OPTO11") (pin "1") (pinfunction "A_1") (pintype "passive"))
      (node (ref "Z11") (pin "C") (pinfunction "C_C") (pintype "passive"))
    )
    (net (code "82") (name "Net-(OPTO12-A)") (class "Default")
      (node (ref "LED12") (pin "C") (pinfunction "C_C") (pintype "passive"))
      (node (ref "OPTO12") (pin "1") (pinfunction "A_1") (pintype "passive"))
      (node (ref "Z12") (pin "C") (pinfunction "C_C") (pintype "passive"))
    )
    (net (code "83") (name "Net-(OPTO13-A)") (class "Default")
      (node (ref "LED13") (pin "C") (pinfunction "C_C") (pintype "passive"))
      (node (ref "OPTO13") (pin "1") (pinfunction "A_1") (pintype "passive"))
      (node (ref "Z13") (pin "C") (pinfunction "C_C") (pintype "passive"))
    )
    (net (code "84") (name "Net-(OPTO14-A)") (class "Default")
      (node (ref "LED14") (pin "C") (pinfunction "C_C") (pintype "passive"))
      (node (ref "OPTO14") (pin "1") (pinfunction "A_1") (pintype "passive"))
      (node (ref "Z14") (pin "C") (pinfunction "C_C") (pintype "passive"))
    )
    (net (code "85") (name "Net-(OPTO15-A)") (class "Default")
      (node (ref "LED15") (pin "C") (pinfunction "C_C") (pintype "passive"))
      (node (ref "OPTO15") (pin "1") (pinfunction "A_1") (pintype "passive"))
      (node (ref "Z15") (pin "C") (pinfunction "C_C") (pintype "passive"))
    )
    (net (code "86") (name "Net-(OPTO16-A)") (class "Default")
      (node (ref "LED16") (pin "C") (pinfunction "C_C") (pintype "passive"))
      (node (ref "OPTO16") (pin "1") (pinfunction "A_1") (pintype "passive"))
      (node (ref "Z16") (pin "C") (pinfunction "C_C") (pintype "passive"))
    )
    (net (code "87") (name "Net-(Q1-B)") (class "Default")
      (node (ref "Q1") (pin "1") (pinfunction "B_1") (pintype "passive"))
      (node (ref "U49") (pin "3") (pinfunction "ET_3") (pintype "passive"))
    )
    (net (code "88") (name "Net-(U49-A)") (class "Default")
      (node (ref "D146") (pin "-") (pinfunction "-_-") (pintype "passive"))
      (node (ref "U49") (pin "1") (pinfunction "A_1") (pintype "passive"))
    )
    (net (code "89") (name "Net-(U49-CT)") (class "Default")
      (node (ref "R116") (pin "1") (pinfunction "1_1") (pintype "passive"))
      (node (ref "U49") (pin "4") (pinfunction "CT_4") (pintype "passive"))
    )
    (net (code "90") (name "P1") (class "Default")
      (node (ref "R1") (pin "1") (pinfunction "1_1") (pintype "passive"))
      (node (ref "X1") (pin "8") (pinfunction "1_8") (pintype "passive"))
    )
    (net (code "91") (name "P2") (class "Default")
      (node (ref "R2") (pin "1") (pinfunction "1_1") (pintype "passive"))
      (node (ref "X1") (pin "7") (pinfunction "1_7") (pintype "passive"))
    )
    (net (code "92") (name "P3") (class "Default")
      (node (ref "R3") (pin "1") (pinfunction "1_1") (pintype "passive"))
      (node (ref "X1") (pin "6") (pinfunction "1_6") (pintype "passive"))
    )
    (net (code "93") (name "P4") (class "Default")
      (node (ref "R4") (pin "1") (pinfunction "1_1") (pintype "passive"))
      (node (ref "X1") (pin "5") (pinfunction "1_5") (pintype "passive"))
    )
    (net (code "94") (name "P5") (class "Default")
      (node (ref "R5") (pin "1") (pinfunction "1_1") (pintype "passive"))
      (node (ref "X1") (pin "4") (pinfunction "1_4") (pintype "passive"))
    )
    (net (code "95") (name "P6") (class "Default")
      (node (ref "R6") (pin "1") (pinfunction "1_1") (pintype "passive"))
      (node (ref "X1") (pin "3") (pinfunction "1_3") (pintype "passive"))
    )
    (net (code "96") (name "P7") (class "Default")
      (node (ref "R7") (pin "1") (pinfunction "1_1") (pintype "passive"))
      (node (ref "X1") (pin "2") (pinfunction "1_2") (pintype "passive"))
    )
    (net (code "97") (name "P8") (class "Default")
      (node (ref "R8") (pin "1") (pinfunction "1_1") (pintype "passive"))
      (node (ref "X1") (pin "1") (pinfunction "1_1") (pintype "passive"))
    )
    (net (code "98") (name "P9") (class "Default")
      (node (ref "R9") (pin "1") (pinfunction "1_1") (pintype "passive"))
      (node (ref "X2") (pin "1") (pinfunction "1_1") (pintype "passive"))
    )
    (net (code "99") (name "P10") (class "Default")
      (node (ref "R10") (pin "1") (pinfunction "1_1") (pintype "passive"))
      (node (ref "X2") (pin "2") (pinfunction "1_2") (pintype "passive"))
    )
    (net (code "100") (name "P11") (class "Default")
      (node (ref "R11") (pin "1") (pinfunction "1_1") (pintype "passive"))
      (node (ref "X2") (pin "3") (pinfunction "1_3") (pintype "passive"))
    )
    (net (code "101") (name "P12") (class "Default")
      (node (ref "R12") (pin "1") (pinfunction "1_1") (pintype "passive"))
      (node (ref "X2") (pin "4") (pinfunction "1_4") (pintype "passive"))
    )
    (net (code "102") (name "P13") (class "Default")
      (node (ref "R13") (pin "1") (pinfunction "1_1") (pintype "passive"))
      (node (ref "X2") (pin "5") (pinfunction "1_5") (pintype "passive"))
    )
    (net (code "103") (name "P14") (class "Default")
      (node (ref "R14") (pin "1") (pinfunction "1_1") (pintype "passive"))
      (node (ref "X2") (pin "6") (pinfunction "1_6") (pintype "passive"))
    )
    (net (code "104") (name "P15") (class "Default")
      (node (ref "R15") (pin "1") (pinfunction "1_1") (pintype "passive"))
      (node (ref "X2") (pin "7") (pinfunction "1_7") (pintype "passive"))
    )
    (net (code "105") (name "P16") (class "Default")
      (node (ref "R16") (pin "1") (pinfunction "1_1") (pintype "passive"))
      (node (ref "X2") (pin "8") (pinfunction "1_8") (pintype "passive"))
    )
    (net (code "106") (name "RELAY") (class "Default")
      (node (ref "R115") (pin "2") (pinfunction "2_2") (pintype "passive"))
      (node (ref "SV2") (pin "1") (pinfunction "1_1") (pintype "passive"))
    )
    (net (code "107") (name "VCC") (class "Default")
      (node (ref "D1") (pin "C") (pinfunction "K_C") (pintype "passive"))
      (node (ref "IC4") (pin "9") (pinfunction "VDD_9") (pintype "power_in"))
      (node (ref "JP2") (pin "1") (pinfunction "1_1") (pintype "passive"))
      (node (ref "JP2") (pin "3") (pinfunction "3_3") (pintype "passive"))
      (node (ref "JP2") (pin "5") (pinfunction "5_5") (pintype "passive"))
      (node (ref "JP2") (pin "7") (pinfunction "7_7") (pintype "passive"))
      (node (ref "K2") (pin "1") (pinfunction "1_1") (pintype "passive"))
      (node (ref "R103") (pin "1") (pinfunction "1_1") (pintype "passive"))
      (node (ref "R116") (pin "2") (pinfunction "2_2") (pintype "passive"))
      (node (ref "R49") (pin "2") (pinfunction "2_2") (pintype "passive"))
      (node (ref "R50") (pin "2") (pinfunction "2_2") (pintype "passive"))
      (node (ref "R51") (pin "2") (pinfunction "2_2") (pintype "passive"))
      (node (ref "R52") (pin "2") (pinfunction "2_2") (pintype "passive"))
      (node (ref "R53") (pin "2") (pinfunction "2_2") (pintype "passive"))
      (node (ref "R54") (pin "2") (pinfunction "2_2") (pintype "passive"))
      (node (ref "R55") (pin "2") (pinfunction "2_2") (pintype "passive"))
      (node (ref "R56") (pin "2") (pinfunction "2_2") (pintype "passive"))
      (node (ref "R57") (pin "2") (pinfunction "2_2") (pintype "passive"))
      (node (ref "R58") (pin "2") (pinfunction "2_2") (pintype "passive"))
      (node (ref "R59") (pin "2") (pinfunction "2_2") (pintype "passive"))
      (node (ref "R60") (pin "2") (pinfunction "2_2") (pintype "passive"))
      (node (ref "R61") (pin "2") (pinfunction "2_2") (pintype "passive"))
      (node (ref "R62") (pin "2") (pinfunction "2_2") (pintype "passive"))
      (node (ref "R63") (pin "2") (pinfunction "2_2") (pintype "passive"))
      (node (ref "R64") (pin "2") (pinfunction "2_2") (pintype "passive"))
      (node (ref "R97") (pin "2") (pinfunction "2_2") (pintype "passive"))
      (node (ref "R98") (pin "2") (pinfunction "2_2") (pintype "passive"))
      (node (ref "TTL-RS1") (pin "VCC") (pinfunction "VCC_VCC") (pintype "bidirectional"))
    )
    (net (code "108") (name "unconnected-(IC4-INTA-Pad20)") (class "Default")
      (node (ref "IC4") (pin "20") (pinfunction "INTA_20") (pintype "output"))
    )
    (net (code "109") (name "unconnected-(IC4-INTB-Pad19)") (class "Default")
      (node (ref "IC4") (pin "19") (pinfunction "INTB_19") (pintype "output"))
    )
    (net (code "110") (name "unconnected-(K2C-O-PadO2)") (class "Default")
      (node (ref "K2") (pin "O2") (pinfunction "O_O2") (pintype "passive"))
    )
    (net (code "111") (name "unconnected-(K2C-P-PadP2)") (class "Default")
      (node (ref "K2") (pin "P2") (pinfunction "P_P2") (pintype "passive"))
    )
    (net (code "112") (name "unconnected-(K2C-S-PadS2)") (class "Default")
      (node (ref "K2") (pin "S2") (pinfunction "S_S2") (pintype "passive"))
    )
  )
)
